# Output_v1_1.net
KiCad netlist of a schematic drawn in EAGLE
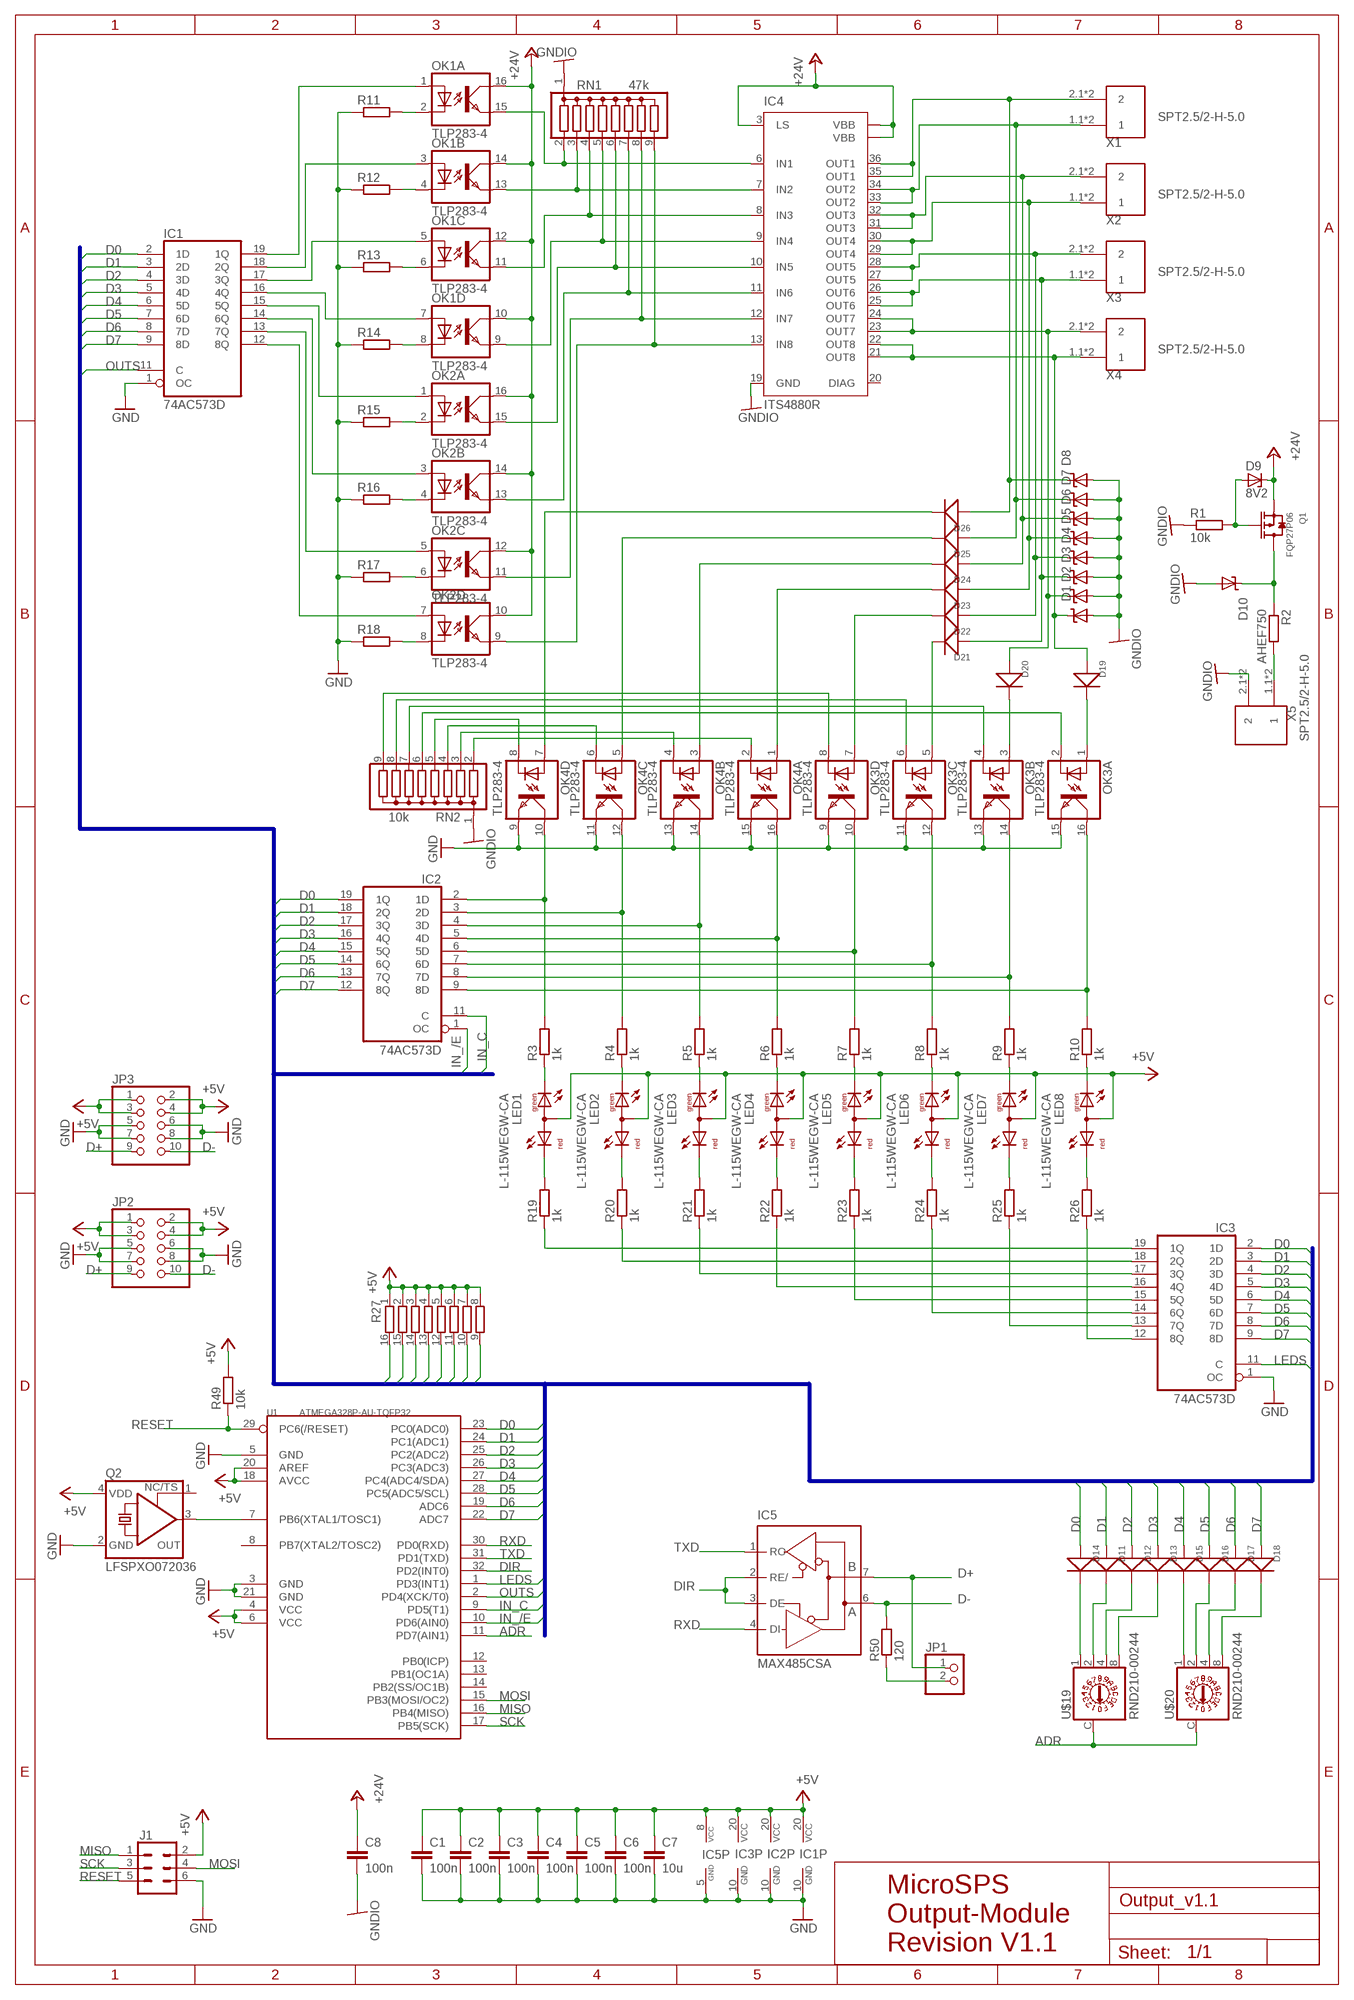
[diagram p0: schematic, sheet 1]

(export (version "E")
  (design (tool "Eeschema 10.0.6"))
  (components
    (comp (ref "C1")
      (value "100n")
      (footprint "eagle-import:C0805")
      (libsource (lib "eagle-import") (part "C-EUC0805"))
    )
    (comp (ref "C2")
      (value "100n")
      (footprint "eagle-import:C0805")
      (libsource (lib "eagle-import") (part "C-EUC0805"))
    )
    (comp (ref "C3")
      (value "100n")
      (footprint "eagle-import:C0805")
      (libsource (lib "eagle-import") (part "C-EUC0805"))
    )
    (comp (ref "C4")
      (value "100n")
      (footprint "eagle-import:C0805")
      (libsource (lib "eagle-import") (part "C-EUC0805"))
    )
    (comp (ref "C5")
      (value "100n")
      (footprint "eagle-import:C0805")
      (libsource (lib "eagle-import") (part "C-EUC0805"))
    )
    (comp (ref "C6")
      (value "100n")
      (footprint "eagle-import:C0805")
      (libsource (lib "eagle-import") (part "C-EUC0805"))
    )
    (comp (ref "C7")
      (value "10u")
      (footprint "eagle-import:C0805")
      (libsource (lib "eagle-import") (part "C-EUC0805"))
    )
    (comp (ref "C8")
      (value "100n")
      (footprint "eagle-import:C0805")
      (libsource (lib "eagle-import") (part "C-EUC0805"))
    )
    (comp (ref "D1")
      (value "SUPPRESSOR-SMBJ")
      (footprint "eagle-import:SMBJ")
      (libsource (lib "eagle-import") (part "SUPPRESSOR-SMBJ"))
    )
    (comp (ref "D2")
      (value "SUPPRESSOR-SMBJ")
      (footprint "eagle-import:SMBJ")
      (libsource (lib "eagle-import") (part "SUPPRESSOR-SMBJ"))
    )
    (comp (ref "D3")
      (value "SUPPRESSOR-SMBJ")
      (footprint "eagle-import:SMBJ")
      (libsource (lib "eagle-import") (part "SUPPRESSOR-SMBJ"))
    )
    (comp (ref "D4")
      (value "SUPPRESSOR-SMBJ")
      (footprint "eagle-import:SMBJ")
      (libsource (lib "eagle-import") (part "SUPPRESSOR-SMBJ"))
    )
    (comp (ref "D5")
      (value "SUPPRESSOR-SMBJ")
      (footprint "eagle-import:SMBJ")
      (libsource (lib "eagle-import") (part "SUPPRESSOR-SMBJ"))
    )
    (comp (ref "D6")
      (value "SUPPRESSOR-SMBJ")
      (footprint "eagle-import:SMBJ")
      (libsource (lib "eagle-import") (part "SUPPRESSOR-SMBJ"))
    )
    (comp (ref "D7")
      (value "SUPPRESSOR-SMBJ")
      (footprint "eagle-import:SMBJ")
      (libsource (lib "eagle-import") (part "SUPPRESSOR-SMBJ"))
    )
    (comp (ref "D8")
      (value "SUPPRESSOR-SMBJ")
      (footprint "eagle-import:SMBJ")
      (libsource (lib "eagle-import") (part "SUPPRESSOR-SMBJ"))
    )
    (comp (ref "D9")
      (value "8V2")
      (footprint "eagle-import:SOD80C")
      (libsource (lib "eagle-import") (part "ZENER-DIODESOD80C"))
    )
    (comp (ref "D10")
      (value "SUPPRESSOR-SMBJ")
      (footprint "eagle-import:SMBJ")
      (libsource (lib "eagle-import") (part "SUPPRESSOR-SMBJ"))
    )
    (comp (ref "D11")
      (value "DIODE'1N4148-SMD'")
      (footprint "eagle-import:LL-34")
      (libsource (lib "eagle-import") (part "DIODE'1N4148-SMD'"))
    )
    (comp (ref "D12")
      (value "DIODE'1N4148-SMD'")
      (footprint "eagle-import:LL-34")
      (libsource (lib "eagle-import") (part "DIODE'1N4148-SMD'"))
    )
    (comp (ref "D13")
      (value "DIODE'1N4148-SMD'")
      (footprint "eagle-import:LL-34")
      (libsource (lib "eagle-import") (part "DIODE'1N4148-SMD'"))
    )
    (comp (ref "D14")
      (value "DIODE'1N4148-SMD'")
      (footprint "eagle-import:LL-34")
      (libsource (lib "eagle-import") (part "DIODE'1N4148-SMD'"))
    )
    (comp (ref "D15")
      (value "DIODE'1N4148-SMD'")
      (footprint "eagle-import:LL-34")
      (libsource (lib "eagle-import") (part "DIODE'1N4148-SMD'"))
    )
    (comp (ref "D16")
      (value "DIODE'1N4148-SMD'")
      (footprint "eagle-import:LL-34")
      (libsource (lib "eagle-import") (part "DIODE'1N4148-SMD'"))
    )
    (comp (ref "D17")
      (value "DIODE'1N4148-SMD'")
      (footprint "eagle-import:LL-34")
      (libsource (lib "eagle-import") (part "DIODE'1N4148-SMD'"))
    )
    (comp (ref "D18")
      (value "DIODE'1N4148-SMD'")
      (footprint "eagle-import:LL-34")
      (libsource (lib "eagle-import") (part "DIODE'1N4148-SMD'"))
    )
    (comp (ref "D19")
      (value "DIODE'1N4148-SMD'")
      (footprint "eagle-import:LL-34")
      (libsource (lib "eagle-import") (part "DIODE'1N4148-SMD'"))
    )
    (comp (ref "D20")
      (value "DIODE'1N4148-SMD'")
      (footprint "eagle-import:LL-34")
      (libsource (lib "eagle-import") (part "DIODE'1N4148-SMD'"))
    )
    (comp (ref "D21")
      (value "DIODE'1N4148-SMD'")
      (footprint "eagle-import:LL-34")
      (libsource (lib "eagle-import") (part "DIODE'1N4148-SMD'"))
    )
    (comp (ref "D22")
      (value "DIODE'1N4148-SMD'")
      (footprint "eagle-import:LL-34")
      (libsource (lib "eagle-import") (part "DIODE'1N4148-SMD'"))
    )
    (comp (ref "D23")
      (value "DIODE'1N4148-SMD'")
      (footprint "eagle-import:LL-34")
      (libsource (lib "eagle-import") (part "DIODE'1N4148-SMD'"))
    )
    (comp (ref "D24")
      (value "DIODE'1N4148-SMD'")
      (footprint "eagle-import:LL-34")
      (libsource (lib "eagle-import") (part "DIODE'1N4148-SMD'"))
    )
    (comp (ref "D25")
      (value "DIODE'1N4148-SMD'")
      (footprint "eagle-import:LL-34")
      (libsource (lib "eagle-import") (part "DIODE'1N4148-SMD'"))
    )
    (comp (ref "D26")
      (value "DIODE'1N4148-SMD'")
      (footprint "eagle-import:LL-34")
      (libsource (lib "eagle-import") (part "DIODE'1N4148-SMD'"))
    )
    (comp (ref "IC1")
      (value "74AC573D")
      (footprint "eagle-import:SO20W")
      (libsource (lib "eagle-import") (part "74573DAC"))
    )
    (comp (ref "IC2")
      (value "74AC573D")
      (footprint "eagle-import:SO20W")
      (libsource (lib "eagle-import") (part "74573DAC"))
    )
    (comp (ref "IC3")
      (value "74AC573D")
      (footprint "eagle-import:SO20W")
      (libsource (lib "eagle-import") (part "74573DAC"))
    )
    (comp (ref "IC4")
      (value "ITS4880R")
      (footprint "eagle-import:PG-DSO-36")
      (libsource (lib "eagle-import") (part "ITS4880R"))
    )
    (comp (ref "IC5")
      (value "MAX485CSA")
      (footprint "eagle-import:SO08")
      (fields (field (name "MF") "MAXIM") (field (name "MPN") "MAX481CSA"))
      (libsource (lib "eagle-import") (part "MAX481CSA"))
    )
    (comp (ref "J1")
      (value "CONN_03X2FEMALE_SMD")
      (footprint "eagle-import:2X3_SMD")
      (libsource (lib "eagle-import") (part "CONN_03X2FEMALE_SMD"))
    )
    (comp (ref "JP1")
      (value "PINHD-1X2")
      (footprint "eagle-import:1X02")
      (libsource (lib "eagle-import") (part "PINHD-1X2"))
    )
    (comp (ref "JP2")
      (value "PINHD-2X5/90")
      (footprint "eagle-import:2X05_90")
      (libsource (lib "eagle-import") (part "PINHD-2X5/90"))
    )
    (comp (ref "JP3")
      (value "PINHD-2X5/90")
      (footprint "eagle-import:2X05_90")
      (libsource (lib "eagle-import") (part "PINHD-2X5/90"))
    )
    (comp (ref "LED1")
      (value "L-115WEGW-CA")
      (footprint "eagle-import:DUOLED-A-3MM")
      (libsource (lib "eagle-import") (part "L-115WEGW-CA"))
    )
    (comp (ref "LED2")
      (value "L-115WEGW-CA")
      (footprint "eagle-import:DUOLED-A-3MM")
      (libsource (lib "eagle-import") (part "L-115WEGW-CA"))
    )
    (comp (ref "LED3")
      (value "L-115WEGW-CA")
      (footprint "eagle-import:DUOLED-A-3MM")
      (libsource (lib "eagle-import") (part "L-115WEGW-CA"))
    )
    (comp (ref "LED4")
      (value "L-115WEGW-CA")
      (footprint "eagle-import:DUOLED-A-3MM")
      (libsource (lib "eagle-import") (part "L-115WEGW-CA"))
    )
    (comp (ref "LED5")
      (value "L-115WEGW-CA")
      (footprint "eagle-import:DUOLED-A-3MM")
      (libsource (lib "eagle-import") (part "L-115WEGW-CA"))
    )
    (comp (ref "LED6")
      (value "L-115WEGW-CA")
      (footprint "eagle-import:DUOLED-A-3MM")
      (libsource (lib "eagle-import") (part "L-115WEGW-CA"))
    )
    (comp (ref "LED7")
      (value "L-115WEGW-CA")
      (footprint "eagle-import:DUOLED-A-3MM")
      (libsource (lib "eagle-import") (part "L-115WEGW-CA"))
    )
    (comp (ref "LED8")
      (value "L-115WEGW-CA")
      (footprint "eagle-import:DUOLED-A-3MM")
      (libsource (lib "eagle-import") (part "L-115WEGW-CA"))
    )
    (comp (ref "OK1")
      (value "TLP283-4")
      (footprint "eagle-import:MINI-FLAT-16")
      (libsource (lib "eagle-import") (part "TLP283-4"))
    )
    (comp (ref "OK2")
      (value "TLP283-4")
      (footprint "eagle-import:MINI-FLAT-16")
      (libsource (lib "eagle-import") (part "TLP283-4"))
    )
    (comp (ref "OK3")
      (value "TLP283-4")
      (footprint "eagle-import:MINI-FLAT-16")
      (libsource (lib "eagle-import") (part "TLP283-4"))
    )
    (comp (ref "OK4")
      (value "TLP283-4")
      (footprint "eagle-import:MINI-FLAT-16")
      (libsource (lib "eagle-import") (part "TLP283-4"))
    )
    (comp (ref "Q1")
      (value "FQP27P06")
      (footprint "eagle-import:TO-220V")
      (libsource (lib "eagle-import") (part "DIP-MOSFET-P-CH-60V-27A-FQP27P06(TO-220)TO-220V"))
    )
    (comp (ref "Q2")
      (value "LFSPXO072036")
      (footprint "eagle-import:5.0X3.2_KXO-56")
      (libsource (lib "eagle-import") (part "KXO-PXO/XO-56-56"))
    )
    (comp (ref "R1")
      (value "10k")
      (footprint "eagle-import:R0805")
      (libsource (lib "eagle-import") (part "R-EU_R0805"))
    )
    (comp (ref "R2")
      (value "AHEF750")
      (footprint "eagle-import:0204_7")
      (libsource (lib "eagle-import") (part "resistor_R-EU_0204/7"))
    )
    (comp (ref "R3")
      (value "1k")
      (footprint "eagle-import:R0805")
      (libsource (lib "eagle-import") (part "R-EU_R0805"))
    )
    (comp (ref "R4")
      (value "1k")
      (footprint "eagle-import:R0805")
      (libsource (lib "eagle-import") (part "R-EU_R0805"))
    )
    (comp (ref "R5")
      (value "1k")
      (footprint "eagle-import:R0805")
      (libsource (lib "eagle-import") (part "R-EU_R0805"))
    )
    (comp (ref "R6")
      (value "1k")
      (footprint "eagle-import:R0805")
      (libsource (lib "eagle-import") (part "R-EU_R0805"))
    )
    (comp (ref "R7")
      (value "1k")
      (footprint "eagle-import:R0805")
      (libsource (lib "eagle-import") (part "R-EU_R0805"))
    )
    (comp (ref "R8")
      (value "1k")
      (footprint "eagle-import:R0805")
      (libsource (lib "eagle-import") (part "R-EU_R0805"))
    )
    (comp (ref "R9")
      (value "1k")
      (footprint "eagle-import:R0805")
      (libsource (lib "eagle-import") (part "R-EU_R0805"))
    )
    (comp (ref "R10")
      (value "1k")
      (footprint "eagle-import:R0805")
      (libsource (lib "eagle-import") (part "R-EU_R0805"))
    )
    (comp (ref "R11")
      (value "R-EU_R0805")
      (footprint "eagle-import:R0805")
      (libsource (lib "eagle-import") (part "R-EU_R0805"))
    )
    (comp (ref "R12")
      (value "R-EU_R0805")
      (footprint "eagle-import:R0805")
      (libsource (lib "eagle-import") (part "R-EU_R0805"))
    )
    (comp (ref "R13")
      (value "R-EU_R0805")
      (footprint "eagle-import:R0805")
      (libsource (lib "eagle-import") (part "R-EU_R0805"))
    )
    (comp (ref "R14")
      (value "R-EU_R0805")
      (footprint "eagle-import:R0805")
      (libsource (lib "eagle-import") (part "R-EU_R0805"))
    )
    (comp (ref "R15")
      (value "R-EU_R0805")
      (footprint "eagle-import:R0805")
      (libsource (lib "eagle-import") (part "R-EU_R0805"))
    )
    (comp (ref "R16")
      (value "R-EU_R0805")
      (footprint "eagle-import:R0805")
      (libsource (lib "eagle-import") (part "R-EU_R0805"))
    )
    (comp (ref "R17")
      (value "R-EU_R0805")
      (footprint "eagle-import:R0805")
      (libsource (lib "eagle-import") (part "R-EU_R0805"))
    )
    (comp (ref "R18")
      (value "R-EU_R0805")
      (footprint "eagle-import:R0805")
      (libsource (lib "eagle-import") (part "R-EU_R0805"))
    )
    (comp (ref "R19")
      (value "1k")
      (footprint "eagle-import:R0805")
      (libsource (lib "eagle-import") (part "R-EU_R0805"))
    )
    (comp (ref "R20")
      (value "1k")
      (footprint "eagle-import:R0805")
      (libsource (lib "eagle-import") (part "R-EU_R0805"))
    )
    (comp (ref "R21")
      (value "1k")
      (footprint "eagle-import:R0805")
      (libsource (lib "eagle-import") (part "R-EU_R0805"))
    )
    (comp (ref "R22")
      (value "1k")
      (footprint "eagle-import:R0805")
      (libsource (lib "eagle-import") (part "R-EU_R0805"))
    )
    (comp (ref "R23")
      (value "1k")
      (footprint "eagle-import:R0805")
      (libsource (lib "eagle-import") (part "R-EU_R0805"))
    )
    (comp (ref "R24")
      (value "1k")
      (footprint "eagle-import:R0805")
      (libsource (lib "eagle-import") (part "R-EU_R0805"))
    )
    (comp (ref "R25")
      (value "1k")
      (footprint "eagle-import:R0805")
      (libsource (lib "eagle-import") (part "R-EU_R0805"))
    )
    (comp (ref "R26")
      (value "1k")
      (footprint "eagle-import:R0805")
      (libsource (lib "eagle-import") (part "R-EU_R0805"))
    )
    (comp (ref "R27")
      (value "4816P-T01")
      (footprint "eagle-import:4816P")
      (fields (field (name "MF") "BOURNS, INC.") (field (name "MPN") "4816P-T01-684LF"))
      (libsource (lib "eagle-import") (part "4816P-T01"))
    )
    (comp (ref "R49")
      (value "10k")
      (footprint "eagle-import:R0805")
      (libsource (lib "eagle-import") (part "R-EU_R0805"))
    )
    (comp (ref "R50")
      (value "120")
      (footprint "eagle-import:R0805")
      (libsource (lib "eagle-import") (part "R-EU_R0805"))
    )
    (comp (ref "RN1")
      (value "47k")
      (footprint "eagle-import:SIL9")
      (libsource (lib "eagle-import") (part "G08R"))
    )
    (comp (ref "RN2")
      (value "10k")
      (footprint "eagle-import:SIL9")
      (libsource (lib "eagle-import") (part "G08R"))
    )
    (comp (ref "U$19")
      (value "RND210-00244")
      (footprint "eagle-import:RND210-00244")
      (libsource (lib "eagle-import") (part "RND210-00244"))
    )
    (comp (ref "U$20")
      (value "RND210-00244")
      (footprint "eagle-import:RND210-00244")
      (libsource (lib "eagle-import") (part "RND210-00244"))
    )
    (comp (ref "U1")
      (value "ATMEGA328P-AU-TQFP32")
      (footprint "eagle-import:TQFP32-0.8-7X7MM")
      (fields (field (name "MPN") "ATMEGA328P-AU"))
      (libsource (lib "eagle-import") (part "MCU-ATMEGA328P-AU(TQFP32)"))
    )
    (comp (ref "X1")
      (value "SPT2.5/2-H-5.0")
      (footprint "eagle-import:SPT2")
      (libsource (lib "eagle-import") (part "SPT2.5/2-H-5.0"))
    )
    (comp (ref "X2")
      (value "SPT2.5/2-H-5.0")
      (footprint "eagle-import:SPT2")
      (libsource (lib "eagle-import") (part "SPT2.5/2-H-5.0"))
    )
    (comp (ref "X3")
      (value "SPT2.5/2-H-5.0")
      (footprint "eagle-import:SPT2")
      (libsource (lib "eagle-import") (part "SPT2.5/2-H-5.0"))
    )
    (comp (ref "X4")
      (value "SPT2.5/2-H-5.0")
      (footprint "eagle-import:SPT2")
      (libsource (lib "eagle-import") (part "SPT2.5/2-H-5.0"))
    )
    (comp (ref "X5")
      (value "SPT2.5/2-H-5.0")
      (footprint "eagle-import:SPT2")
      (libsource (lib "eagle-import") (part "SPT2.5/2-H-5.0"))
    )
  )
  (nets
    (net (code "1") (name "+5V") (class "Default")
      (node (ref "C1") (pin "1") (pinfunction "1_1") (pintype "passive"))
      (node (ref "C2") (pin "1") (pinfunction "1_1") (pintype "passive"))
      (node (ref "C3") (pin "1") (pinfunction "1_1") (pintype "passive"))
      (node (ref "C4") (pin "1") (pinfunction "1_1") (pintype "passive"))
      (node (ref "C5") (pin "1") (pinfunction "1_1") (pintype "passive"))
      (node (ref "C6") (pin "1") (pinfunction "1_1") (pintype "passive"))
      (node (ref "C7") (pin "1") (pinfunction "1_1") (pintype "passive"))
      (node (ref "IC1") (pin "20") (pinfunction "VCC_20") (pintype "power_in"))
      (node (ref "IC2") (pin "20") (pinfunction "VCC_20") (pintype "power_in"))
      (node (ref "IC3") (pin "20") (pinfunction "VCC_20") (pintype "power_in"))
      (node (ref "IC5") (pin "8") (pinfunction "VCC_8") (pintype "power_in"))
      (node (ref "J1") (pin "2") (pinfunction "2_2") (pintype "bidirectional"))
      (node (ref "JP2") (pin "1") (pinfunction "1_1") (pintype "passive"))
      (node (ref "JP2") (pin "2") (pinfunction "2_2") (pintype "passive"))
      (node (ref "JP2") (pin "3") (pinfunction "3_3") (pintype "passive"))
      (node (ref "JP2") (pin "4") (pinfunction "4_4") (pintype "passive"))
      (node (ref "JP3") (pin "1") (pinfunction "1_1") (pintype "passive"))
      (node (ref "JP3") (pin "2") (pinfunction "2_2") (pintype "passive"))
      (node (ref "JP3") (pin "3") (pinfunction "3_3") (pintype "passive"))
      (node (ref "JP3") (pin "4") (pinfunction "4_4") (pintype "passive"))
      (node (ref "LED1") (pin "2") (pinfunction "A_2") (pintype "passive"))
      (node (ref "LED2") (pin "2") (pinfunction "A_2") (pintype "passive"))
      (node (ref "LED3") (pin "2") (pinfunction "A_2") (pintype "passive"))
      (node (ref "LED4") (pin "2") (pinfunction "A_2") (pintype "passive"))
      (node (ref "LED5") (pin "2") (pinfunction "A_2") (pintype "passive"))
      (node (ref "LED6") (pin "2") (pinfunction "A_2") (pintype "passive"))
      (node (ref "LED7") (pin "2") (pinfunction "A_2") (pintype "passive"))
      (node (ref "LED8") (pin "2") (pinfunction "A_2") (pintype "passive"))
      (node (ref "Q2") (pin "4") (pinfunction "VDD_4") (pintype "power_in"))
      (node (ref "R27") (pin "1") (pinfunction "1_1") (pintype "passive"))
      (node (ref "R27") (pin "2") (pinfunction "2_2") (pintype "passive"))
      (node (ref "R27") (pin "3") (pinfunction "3_3") (pintype "passive"))
      (node (ref "R27") (pin "4") (pinfunction "4_4") (pintype "passive"))
      (node (ref "R27") (pin "5") (pinfunction "5_5") (pintype "passive"))
      (node (ref "R27") (pin "6") (pinfunction "6_6") (pintype "passive"))
      (node (ref "R27") (pin "7") (pinfunction "7_7") (pintype "passive"))
      (node (ref "R27") (pin "8") (pinfunction "8_8") (pintype "passive"))
      (node (ref "R49") (pin "2") (pinfunction "2_2") (pintype "passive"))
      (node (ref "U1") (pin "18") (pinfunction "AVCC_18") (pintype "bidirectional"))
      (node (ref "U1") (pin "20") (pinfunction "AREF_20") (pintype "bidirectional"))
      (node (ref "U1") (pin "4") (pinfunction "VCC_4") (pintype "bidirectional"))
      (node (ref "U1") (pin "6") (pinfunction "VCC_6") (pintype "bidirectional"))
    )
    (net (code "2") (name "+24V") (class "Default")
      (node (ref "C8") (pin "1") (pinfunction "1_1") (pintype "passive"))
      (node (ref "D9") (pin "C") (pinfunction "C_C") (pintype "passive"))
      (node (ref "IC4") (pin "3") (pinfunction "LS_3") (pintype "input"))
      (node (ref "IC4") (pin "TH@1") (pinfunction "VBB_TH@1") (pintype "input"))
      (node (ref "IC4") (pin "TH@2") (pinfunction "VBB_TH@2") (pintype "input"))
      (node (ref "OK1") (pin "10") (pinfunction "COL_10") (pintype "passive"))
      (node (ref "OK1") (pin "12") (pinfunction "COL_12") (pintype "passive"))
      (node (ref "OK1") (pin "14") (pinfunction "COL_14") (pintype "passive"))
      (node (ref "OK1") (pin "16") (pinfunction "COL_16") (pintype "passive"))
      (node (ref "OK2") (pin "10") (pinfunction "COL_10") (pintype "passive"))
      (node (ref "OK2") (pin "12") (pinfunction "COL_12") (pintype "passive"))
      (node (ref "OK2") (pin "14") (pinfunction "COL_14") (pintype "passive"))
      (node (ref "OK2") (pin "16") (pinfunction "COL_16") (pintype "passive"))
      (node (ref "Q1") (pin "3") (pinfunction "S_3") (pintype "passive"))
    )
    (net (code "3") (name "/ADR") (class "Default")
      (node (ref "U$19") (pin "C") (pinfunction "C_C") (pintype "passive"))
      (node (ref "U$20") (pin "C") (pinfunction "C_C") (pintype "passive"))
      (node (ref "U1") (pin "11") (pinfunction "PD7(AIN1)_11") (pintype "bidirectional"))
    )
    (net (code "4") (name "/D+") (class "Default")
      (node (ref "IC5") (pin "7") (pinfunction "B_7") (pintype "passive"))
      (node (ref "JP1") (pin "1") (pinfunction "1_1") (pintype "passive"))
      (node (ref "JP2") (pin "9") (pinfunction "9_9") (pintype "passive"))
      (node (ref "JP3") (pin "9") (pinfunction "9_9") (pintype "passive"))
    )
    (net (code "5") (name "/D-") (class "Default")
      (node (ref "IC5") (pin "6") (pinfunction "A_6") (pintype "passive"))
      (node (ref "JP2") (pin "10") (pinfunction "10_10") (pintype "passive"))
      (node (ref "JP3") (pin "10") (pinfunction "10_10") (pintype "passive"))
      (node (ref "R50") (pin "2") (pinfunction "2_2") (pintype "passive"))
    )
    (net (code "6") (name "/D0") (class "Default")
      (node (ref "D14") (pin "A") (pinfunction "+_A") (pintype "passive"))
      (node (ref "IC1") (pin "2") (pinfunction "1D_2") (pintype "input"))
      (node (ref "IC2") (pin "19") (pinfunction "1Q_19") (pintype "tri_state"))
      (node (ref "IC3") (pin "2") (pinfunction "1D_2") (pintype "input"))
      (node (ref "R27") (pin "16") (pinfunction "16_16") (pintype "passive"))
      (node (ref "U1") (pin "23") (pinfunction "PC0(ADC0)_23") (pintype "bidirectional"))
    )
    (net (code "7") (name "/D1") (class "Default")
      (node (ref "D11") (pin "A") (pinfunction "+_A") (pintype "passive"))
      (node (ref "IC1") (pin "3") (pinfunction "2D_3") (pintype "input"))
      (node (ref "IC2") (pin "18") (pinfunction "2Q_18") (pintype "tri_state"))
      (node (ref "IC3") (pin "3") (pinfunction "2D_3") (pintype "input"))
      (node (ref "R27") (pin "15") (pinfunction "15_15") (pintype "passive"))
      (node (ref "U1") (pin "24") (pinfunction "PC1(ADC1)_24") (pintype "bidirectional"))
    )
    (net (code "8") (name "/D2") (class "Default")
      (node (ref "D12") (pin "A") (pinfunction "+_A") (pintype "passive"))
      (node (ref "IC1") (pin "4") (pinfunction "3D_4") (pintype "input"))
      (node (ref "IC2") (pin "17") (pinfunction "3Q_17") (pintype "tri_state"))
      (node (ref "IC3") (pin "4") (pinfunction "3D_4") (pintype "input"))
      (node (ref "R27") (pin "14") (pinfunction "14_14") (pintype "passive"))
      (node (ref "U1") (pin "25") (pinfunction "PC2(ADC2)_25") (pintype "bidirectional"))
    )
    (net (code "9") (name "/D3") (class "Default")
      (node (ref "D13") (pin "A") (pinfunction "+_A") (pintype "passive"))
      (node (ref "IC1") (pin "5") (pinfunction "4D_5") (pintype "input"))
      (node (ref "IC2") (pin "16") (pinfunction "4Q_16") (pintype "tri_state"))
      (node (ref "IC3") (pin "5") (pinfunction "4D_5") (pintype "input"))
      (node (ref "R27") (pin "13") (pinfunction "13_13") (pintype "passive"))
      (node (ref "U1") (pin "26") (pinfunction "PC3(ADC3)_26") (pintype "bidirectional"))
    )
    (net (code "10") (name "/D4") (class "Default")
      (node (ref "D15") (pin "A") (pinfunction "+_A") (pintype "passive"))
      (node (ref "IC1") (pin "6") (pinfunction "5D_6") (pintype "input"))
      (node (ref "IC2") (pin "15") (pinfunction "5Q_15") (pintype "tri_state"))
      (node (ref "IC3") (pin "6") (pinfunction "5D_6") (pintype "input"))
      (node (ref "R27") (pin "12") (pinfunction "12_12") (pintype "passive"))
      (node (ref "U1") (pin "27") (pinfunction "PC4(ADC4/SDA)_27") (pintype "bidirectional"))
    )
    (net (code "11") (name "/D5") (class "Default")
      (node (ref "D16") (pin "A") (pinfunction "+_A") (pintype "passive"))
      (node (ref "IC1") (pin "7") (pinfunction "6D_7") (pintype "input"))
      (node (ref "IC2") (pin "14") (pinfunction "6Q_14") (pintype "tri_state"))
      (node (ref "IC3") (pin "7") (pinfunction "6D_7") (pintype "input"))
      (node (ref "R27") (pin "11") (pinfunction "11_11") (pintype "passive"))
      (node (ref "U1") (pin "28") (pinfunction "PC5(ADC5/SCL)_28") (pintype "bidirectional"))
    )
    (net (code "12") (name "/D6") (class "Default")
      (node (ref "D17") (pin "A") (pinfunction "+_A") (pintype "passive"))
      (node (ref "IC1") (pin "8") (pinfunction "7D_8") (pintype "input"))
      (node (ref "IC2") (pin "13") (pinfunction "7Q_13") (pintype "tri_state"))
      (node (ref "IC3") (pin "8") (pinfunction "7D_8") (pintype "input"))
      (node (ref "R27") (pin "10") (pinfunction "10_10") (pintype "passive"))
      (node (ref "U1") (pin "19") (pinfunction "ADC6_19") (pintype "bidirectional"))
    )
    (net (code "13") (name "/D7") (class "Default")
      (node (ref "D18") (pin "A") (pinfunction "+_A") (pintype "passive"))
      (node (ref "IC1") (pin "9") (pinfunction "8D_9") (pintype "input"))
      (node (ref "IC2") (pin "12") (pinfunction "8Q_12") (pintype "tri_state"))
      (node (ref "IC3") (pin "9") (pinfunction "8D_9") (pintype "input"))
      (node (ref "R27") (pin "9") (pinfunction "9_9") (pintype "passive"))
      (node (ref "U1") (pin "22") (pinfunction "ADC7_22") (pintype "bidirectional"))
    )
    (net (code "14") (name "/DIR") (class "Default")
      (node (ref "IC5") (pin "2") (pinfunction "RE/_2") (pintype "input"))
      (node (ref "IC5") (pin "3") (pinfunction "DE_3") (pintype "input"))
      (node (ref "U1") (pin "32") (pinfunction "PD2(INT0)_32") (pintype "bidirectional"))
    )
    (net (code "15") (name "/IN_C") (class "Default")
      (node (ref "IC2") (pin "11") (pinfunction "C_11") (pintype "input"))
      (node (ref "U1") (pin "9") (pinfunction "PD5(T1)_9") (pintype "bidirectional"))
    )
    (net (code "16") (name "/IN_{slash}E") (class "Default")
      (node (ref "IC2") (pin "1") (pinfunction "OC_1") (pintype "input"))
      (node (ref "U1") (pin "10") (pinfunction "PD6(AIN0)_10") (pintype "bidirectional"))
    )
    (net (code "17") (name "/LEDS") (class "Default")
      (node (ref "IC3") (pin "11") (pinfunction "C_11") (pintype "input"))
      (node (ref "U1") (pin "1") (pinfunction "PD3(INT1)_1") (pintype "bidirectional"))
    )
    (net (code "18") (name "/MISO") (class "Default")
      (node (ref "J1") (pin "1") (pinfunction "1_1") (pintype "bidirectional"))
      (node (ref "U1") (pin "16") (pinfunction "PB4(MISO)_16") (pintype "bidirectional"))
    )
    (net (code "19") (name "/MOSI") (class "Default")
      (node (ref "J1") (pin "4") (pinfunction "4_4") (pintype "bidirectional"))
      (node (ref "U1") (pin "15") (pinfunction "PB3(MOSI/OC2)_15") (pintype "bidirectional"))
    )
    (net (code "20") (name "/OUTS") (class "Default")
      (node (ref "IC1") (pin "11") (pinfunction "C_11") (pintype "input"))
      (node (ref "U1") (pin "2") (pinfunction "PD4(XCK/T0)_2") (pintype "bidirectional"))
    )
    (net (code "21") (name "/RESET") (class "Default")
      (node (ref "J1") (pin "5") (pinfunction "5_5") (pintype "bidirectional"))
      (node (ref "R49") (pin "1") (pinfunction "1_1") (pintype "passive"))
      (node (ref "U1") (pin "29") (pinfunction "PC6(/RESET)_29") (pintype "bidirectional"))
    )
    (net (code "22") (name "/RXD") (class "Default")
      (node (ref "IC5") (pin "4") (pinfunction "DI_4") (pintype "input"))
      (node (ref "U1") (pin "30") (pinfunction "PD0(RXD)_30") (pintype "bidirectional"))
    )
    (net (code "23") (name "/SCK") (class "Default")
      (node (ref "J1") (pin "3") (pinfunction "3_3") (pintype "bidirectional"))
      (node (ref "U1") (pin "17") (pinfunction "PB5(SCK)_17") (pintype "bidirectional"))
    )
    (net (code "24") (name "/TXD") (class "Default")
      (node (ref "IC5") (pin "1") (pinfunction "RO_1") (pintype "output"))
      (node (ref "U1") (pin "31") (pinfunction "PD1(TXD)_31") (pintype "bidirectional"))
    )
    (net (code "25") (name "GND") (class "Default")
      (node (ref "C1") (pin "2") (pinfunction "2_2") (pintype "passive"))
      (node (ref "C2") (pin "2") (pinfunction "2_2") (pintype "passive"))
      (node (ref "C3") (pin "2") (pinfunction "2_2") (pintype "passive"))
      (node (ref "C4") (pin "2") (pinfunction "2_2") (pintype "passive"))
      (node (ref "C5") (pin "2") (pinfunction "2_2") (pintype "passive"))
      (node (ref "C6") (pin "2") (pinfunction "2_2") (pintype "passive"))
      (node (ref "C7") (pin "2") (pinfunction "2_2") (pintype "passive"))
      (node (ref "IC1") (pin "1") (pinfunction "OC_1") (pintype "input"))
      (node (ref "IC1") (pin "10") (pinfunction "GND_10") (pintype "power_in"))
      (node (ref "IC2") (pin "10") (pinfunction "GND_10") (pintype "power_in"))
      (node (ref "IC3") (pin "1") (pinfunction "OC_1") (pintype "input"))
      (node (ref "IC3") (pin "10") (pinfunction "GND_10") (pintype "power_in"))
      (node (ref "IC5") (pin "5") (pinfunction "GND_5") (pintype "power_in"))
      (node (ref "J1") (pin "6") (pinfunction "6_6") (pintype "bidirectional"))
      (node (ref "JP2") (pin "5") (pinfunction "5_5") (pintype "passive"))
      (node (ref "JP2") (pin "6") (pinfunction "6_6") (pintype "passive"))
      (node (ref "JP2") (pin "7") (pinfunction "7_7") (pintype "passive"))
      (node (ref "JP2") (pin "8") (pinfunction "8_8") (pintype "passive"))
      (node (ref "JP3") (pin "5") (pinfunction "5_5") (pintype "passive"))
      (node (ref "JP3") (pin "6") (pinfunction "6_6") (pintype "passive"))
      (node (ref "JP3") (pin "7") (pinfunction "7_7") (pintype "passive"))
      (node (ref "JP3") (pin "8") (pinfunction "8_8") (pintype "passive"))
      (node (ref "OK3") (pin "11") (pinfunction "EMIT_11") (pintype "passive"))
      (node (ref "OK3") (pin "13") (pinfunction "EMIT_13") (pintype "passive"))
      (node (ref "OK3") (pin "15") (pinfunction "EMIT_15") (pintype "passive"))
      (node (ref "OK3") (pin "9") (pinfunction "EMIT_9") (pintype "passive"))
      (node (ref "OK4") (pin "11") (pinfunction "EMIT_11") (pintype "passive"))
      (node (ref "OK4") (pin "13") (pinfunction "EMIT_13") (pintype "passive"))
      (node (ref "OK4") (pin "15") (pinfunction "EMIT_15") (pintype "passive"))
      (node (ref "OK4") (pin "9") (pinfunction "EMIT_9") (pintype "passive"))
      (node (ref "Q2") (pin "2") (pinfunction "GND_2") (pintype "power_in"))
      (node (ref "R11") (pin "1") (pinfunction "1_1") (pintype "passive"))
      (node (ref "R12") (pin "1") (pinfunction "1_1") (pintype "passive"))
      (node (ref "R13") (pin "1") (pinfunction "1_1") (pintype "passive"))
      (node (ref "R14") (pin "1") (pinfunction "1_1") (pintype "passive"))
      (node (ref "R15") (pin "1") (pinfunction "1_1") (pintype "passive"))
      (node (ref "R16") (pin "1") (pinfunction "1_1") (pintype "passive"))
      (node (ref "R17") (pin "1") (pinfunction "1_1") (pintype "passive"))
      (node (ref "R18") (pin "1") (pinfunction "1_1") (pintype "passive"))
      (node (ref "U1") (pin "21") (pinfunction "GND_21") (pintype "bidirectional"))
      (node (ref "U1") (pin "3") (pinfunction "GND_3") (pintype "bidirectional"))
      (node (ref "U1") (pin "5") (pinfunction "GND_5") (pintype "bidirectional"))
    )
    (net (code "26") (name "GNDIO") (class "Default")
      (node (ref "C8") (pin "2") (pinfunction "2_2") (pintype "passive"))
      (node (ref "D1") (pin "A") (pinfunction "A_A") (pintype "passive"))
      (node (ref "D10") (pin "A") (pinfunction "A_A") (pintype "passive"))
      (node (ref "D2") (pin "A") (pinfunction "A_A") (pintype "passive"))
      (node (ref "D3") (pin "A") (pinfunction "A_A") (pintype "passive"))
      (node (ref "D4") (pin "A") (pinfunction "A_A") (pintype "passive"))
      (node (ref "D5") (pin "A") (pinfunction "A_A") (pintype "passive"))
      (node (ref "D6") (pin "A") (pinfunction "A_A") (pintype "passive"))
      (node (ref "D7") (pin "A") (pinfunction "A_A") (pintype "passive"))
      (node (ref "D8") (pin "A") (pinfunction "A_A") (pintype "passive"))
      (node (ref "IC4") (pin "19") (pinfunction "GND_19") (pintype "power_in"))
      (node (ref "R1") (pin "1") (pinfunction "1_1") (pintype "passive"))
      (node (ref "RN1") (pin "1") (pinfunction "1_1") (pintype "passive"))
      (node (ref "RN2") (pin "1") (pinfunction "1_1") (pintype "passive"))
      (node (ref "X5") (pin "2.1") (pinfunction "2_2.1") (pintype "bidirectional"))
      (node (ref "X5") (pin "2.2") (pinfunction "2_2.2") (pintype "bidirectional"))
    )
    (net (code "27") (name "Net-(D11--)") (class "Default")
      (node (ref "D11") (pin "C") (pinfunction "-_C") (pintype "passive"))
      (node (ref "U$19") (pin "2") (pinfunction "2_2") (pintype "passive"))
    )
    (net (code "28") (name "Net-(D12--)") (class "Default")
      (node (ref "D12") (pin "C") (pinfunction "-_C") (pintype "passive"))
      (node (ref "U$19") (pin "4") (pinfunction "4_4") (pintype "passive"))
    )
    (net (code "29") (name "Net-(D13--)") (class "Default")
      (node (ref "D13") (pin "C") (pinfunction "-_C") (pintype "passive"))
      (node (ref "U$19") (pin "8") (pinfunction "8_8") (pintype "passive"))
    )
    (net (code "30") (name "Net-(D14--)") (class "Default")
      (node (ref "D14") (pin "C") (pinfunction "-_C") (pintype "passive"))
      (node (ref "U$19") (pin "1") (pinfunction "1_1") (pintype "passive"))
    )
    (net (code "31") (name "Net-(D15--)") (class "Default")
      (node (ref "D15") (pin "C") (pinfunction "-_C") (pintype "passive"))
      (node (ref "U$20") (pin "1") (pinfunction "1_1") (pintype "passive"))
    )
    (net (code "32") (name "Net-(D16--)") (class "Default")
      (node (ref "D16") (pin "C") (pinfunction "-_C") (pintype "passive"))
      (node (ref "U$20") (pin "2") (pinfunction "2_2") (pintype "passive"))
    )
    (net (code "33") (name "Net-(D17--)") (class "Default")
      (node (ref "D17") (pin "C") (pinfunction "-_C") (pintype "passive"))
      (node (ref "U$20") (pin "4") (pinfunction "4_4") (pintype "passive"))
    )
    (net (code "34") (name "Net-(D18--)") (class "Default")
      (node (ref "D18") (pin "C") (pinfunction "-_C") (pintype "passive"))
      (node (ref "U$20") (pin "8") (pinfunction "8_8") (pintype "passive"))
    )
    (net (code "35") (name "Net-(D19-+)") (class "Default")
      (node (ref "D1") (pin "C") (pinfunction "C_C") (pintype "passive"))
      (node (ref "D19") (pin "A") (pinfunction "+_A") (pintype "passive"))
      (node (ref "IC4") (pin "21") (pinfunction "OUT8_21") (pintype "output"))
      (node (ref "IC4") (pin "22") (pinfunction "OUT8_22") (pintype "output"))
      (node (ref "X4") (pin "1.1") (pinfunction "1_1.1") (pintype "bidirectional"))
      (node (ref "X4") (pin "1.2") (pinfunction "1_1.2") (pintype "bidirectional"))
    )
    (net (code "36") (name "Net-(D19--)") (class "Default")
      (node (ref "D19") (pin "C") (pinfunction "-_C") (pintype "passive"))
      (node (ref "OK3") (pin "1") (pinfunction "A_1") (pintype "passive"))
    )
    (net (code "37") (name "Net-(D20-+)") (class "Default")
      (node (ref "D2") (pin "C") (pinfunction "C_C") (pintype "passive"))
      (node (ref "D20") (pin "A") (pinfunction "+_A") (pintype "passive"))
      (node (ref "IC4") (pin "23") (pinfunction "OUT7_23") (pintype "output"))
      (node (ref "IC4") (pin "24") (pinfunction "OUT7_24") (pintype "output"))
      (node (ref "X4") (pin "2.1") (pinfunction "2_2.1") (pintype "bidirectional"))
      (node (ref "X4") (pin "2.2") (pinfunction "2_2.2") (pintype "bidirectional"))
    )
    (net (code "38") (name "Net-(D20--)") (class "Default")
      (node (ref "D20") (pin "C") (pinfunction "-_C") (pintype "passive"))
      (node (ref "OK3") (pin "3") (pinfunction "A_3") (pintype "passive"))
    )
    (net (code "39") (name "Net-(D21-+)") (class "Default")
      (node (ref "D21") (pin "A") (pinfunction "+_A") (pintype "passive"))
      (node (ref "D3") (pin "C") (pinfunction "C_C") (pintype "passive"))
      (node (ref "IC4") (pin "25") (pinfunction "OUT6_25") (pintype "output"))
      (node (ref "IC4") (pin "26") (pinfunction "OUT6_26") (pintype "output"))
      (node (ref "X3") (pin "1.1") (pinfunction "1_1.1") (pintype "bidirectional"))
      (node (ref "X3") (pin "1.2") (pinfunction "1_1.2") (pintype "bidirectional"))
    )
    (net (code "40") (name "Net-(D21--)") (class "Default")
      (node (ref "D21") (pin "C") (pinfunction "-_C") (pintype "passive"))
      (node (ref "OK3") (pin "5") (pinfunction "A_5") (pintype "passive"))
    )
    (net (code "41") (name "Net-(D22-+)") (class "Default")
      (node (ref "D22") (pin "A") (pinfunction "+_A") (pintype "passive"))
      (node (ref "D4") (pin "C") (pinfunction "C_C") (pintype "passive"))
      (node (ref "IC4") (pin "27") (pinfunction "OUT5_27") (pintype "output"))
      (node (ref "IC4") (pin "28") (pinfunction "OUT5_28") (pintype "output"))
      (node (ref "X3") (pin "2.1") (pinfunction "2_2.1") (pintype "bidirectional"))
      (node (ref "X3") (pin "2.2") (pinfunction "2_2.2") (pintype "bidirectional"))
    )
    (net (code "42") (name "Net-(D22--)") (class "Default")
      (node (ref "D22") (pin "C") (pinfunction "-_C") (pintype "passive"))
      (node (ref "OK3") (pin "7") (pinfunction "A_7") (pintype "passive"))
    )
    (net (code "43") (name "Net-(D23-+)") (class "Default")
      (node (ref "D23") (pin "A") (pinfunction "+_A") (pintype "passive"))
      (node (ref "D5") (pin "C") (pinfunction "C_C") (pintype "passive"))
      (node (ref "IC4") (pin "29") (pinfunction "OUT4_29") (pintype "output"))
      (node (ref "IC4") (pin "30") (pinfunction "OUT4_30") (pintype "output"))
      (node (ref "X2") (pin "1.1") (pinfunction "1_1.1") (pintype "bidirectional"))
      (node (ref "X2") (pin "1.2") (pinfunction "1_1.2") (pintype "bidirectional"))
    )
    (net (code "44") (name "Net-(D23--)") (class "Default")
      (node (ref "D23") (pin "C") (pinfunction "-_C") (pintype "passive"))
      (node (ref "OK4") (pin "1") (pinfunction "A_1") (pintype "passive"))
    )
    (net (code "45") (name "Net-(D24-+)") (class "Default")
      (node (ref "D24") (pin "A") (pinfunction "+_A") (pintype "passive"))
      (node (ref "D6") (pin "C") (pinfunction "C_C") (pintype "passive"))
      (node (ref "IC4") (pin "31") (pinfunction "OUT3_31") (pintype "output"))
      (node (ref "IC4") (pin "32") (pinfunction "OUT3_32") (pintype "output"))
      (node (ref "X2") (pin "2.1") (pinfunction "2_2.1") (pintype "bidirectional"))
      (node (ref "X2") (pin "2.2") (pinfunction "2_2.2") (pintype "bidirectional"))
    )
    (net (code "46") (name "Net-(D24--)") (class "Default")
      (node (ref "D24") (pin "C") (pinfunction "-_C") (pintype "passive"))
      (node (ref "OK4") (pin "3") (pinfunction "A_3") (pintype "passive"))
    )
    (net (code "47") (name "Net-(D25-+)") (class "Default")
      (node (ref "D25") (pin "A") (pinfunction "+_A") (pintype "passive"))
      (node (ref "D7") (pin "C") (pinfunction "C_C") (pintype "passive"))
      (node (ref "IC4") (pin "33") (pinfunction "OUT2_33") (pintype "output"))
      (node (ref "IC4") (pin "34") (pinfunction "OUT2_34") (pintype "output"))
      (node (ref "X1") (pin "1.1") (pinfunction "1_1.1") (pintype "bidirectional"))
      (node (ref "X1") (pin "1.2") (pinfunction "1_1.2") (pintype "bidirectional"))
    )
    (net (code "48") (name "Net-(D25--)") (class "Default")
      (node (ref "D25") (pin "C") (pinfunction "-_C") (pintype "passive"))
      (node (ref "OK4") (pin "5") (pinfunction "A_5") (pintype "passive"))
    )
    (net (code "49") (name "Net-(D26-+)") (class "Default")
      (node (ref "D26") (pin "A") (pinfunction "+_A") (pintype "passive"))
      (node (ref "D8") (pin "C") (pinfunction "C_C") (pintype "passive"))
      (node (ref "IC4") (pin "35") (pinfunction "OUT1_35") (pintype "output"))
      (node (ref "IC4") (pin "36") (pinfunction "OUT1_36") (pintype "output"))
      (node (ref "X1") (pin "2.1") (pinfunction "2_2.1") (pintype "bidirectional"))
      (node (ref "X1") (pin "2.2") (pinfunction "2_2.2") (pintype "bidirectional"))
    )
    (net (code "50") (name "Net-(D26--)") (class "Default")
      (node (ref "D26") (pin "C") (pinfunction "-_C") (pintype "passive"))
      (node (ref "OK4") (pin "7") (pinfunction "A_7") (pintype "passive"))
    )
    (net (code "51") (name "Net-(IC1A-1Q)") (class "Default")
      (node (ref "IC1") (pin "19") (pinfunction "1Q_19") (pintype "tri_state"))
      (node (ref "OK1") (pin "1") (pinfunction "A_1") (pintype "passive"))
    )
    (net (code "52") (name "Net-(IC1A-2Q)") (class "Default")
      (node (ref "IC1") (pin "18") (pinfunction "2Q_18") (pintype "tri_state"))
      (node (ref "OK1") (pin "3") (pinfunction "A_3") (pintype "passive"))
    )
    (net (code "53") (name "Net-(IC1A-3Q)") (class "Default")
      (node (ref "IC1") (pin "17") (pinfunction "3Q_17") (pintype "tri_state"))
      (node (ref "OK1") (pin "5") (pinfunction "A_5") (pintype "passive"))
    )
    (net (code "54") (name "Net-(IC1A-4Q)") (class "Default")
      (node (ref "IC1") (pin "16") (pinfunction "4Q_16") (pintype "tri_state"))
      (node (ref "OK1") (pin "7") (pinfunction "A_7") (pintype "passive"))
    )
    (net (code "55") (name "Net-(IC1A-5Q)") (class "Default")
      (node (ref "IC1") (pin "15") (pinfunction "5Q_15") (pintype "tri_state"))
      (node (ref "OK2") (pin "1") (pinfunction "A_1") (pintype "passive"))
    )
    (net (code "56") (name "Net-(IC1A-6Q)") (class "Default")
      (node (ref "IC1") (pin "14") (pinfunction "6Q_14") (pintype "tri_state"))
      (node (ref "OK2") (pin "3") (pinfunction "A_3") (pintype "passive"))
    )
    (net (code "57") (name "Net-(IC1A-7Q)") (class "Default")
      (node (ref "IC1") (pin "13") (pinfunction "7Q_13") (pintype "tri_state"))
      (node (ref "OK2") (pin "5") (pinfunction "A_5") (pintype "passive"))
    )
    (net (code "58") (name "Net-(IC1A-8Q)") (class "Default")
      (node (ref "IC1") (pin "12") (pinfunction "8Q_12") (pintype "tri_state"))
      (node (ref "OK2") (pin "7") (pinfunction "A_7") (pintype "passive"))
    )
    (net (code "59") (name "Net-(IC2A-1D)") (class "Default")
      (node (ref "IC2") (pin "2") (pinfunction "1D_2") (pintype "input"))
      (node (ref "OK4") (pin "10") (pinfunction "COL_10") (pintype "passive"))
      (node (ref "R3") (pin "2") (pinfunction "2_2") (pintype "passive"))
    )
    (net (code "60") (name "Net-(IC2A-2D)") (class "Default")
      (node (ref "IC2") (pin "3") (pinfunction "2D_3") (pintype "input"))
      (node (ref "OK4") (pin "12") (pinfunction "COL_12") (pintype "passive"))
      (node (ref "R4") (pin "2") (pinfunction "2_2") (pintype "passive"))
    )
    (net (code "61") (name "Net-(IC2A-3D)") (class "Default")
      (node (ref "IC2") (pin "4") (pinfunction "3D_4") (pintype "input"))
      (node (ref "OK4") (pin "14") (pinfunction "COL_14") (pintype "passive"))
      (node (ref "R5") (pin "2") (pinfunction "2_2") (pintype "passive"))
    )
    (net (code "62") (name "Net-(IC2A-4D)") (class "Default")
      (node (ref "IC2") (pin "5") (pinfunction "4D_5") (pintype "input"))
      (node (ref "OK4") (pin "16") (pinfunction "COL_16") (pintype "passive"))
      (node (ref "R6") (pin "2") (pinfunction "2_2") (pintype "passive"))
    )
    (net (code "63") (name "Net-(IC2A-5D)") (class "Default")
      (node (ref "IC2") (pin "6") (pinfunction "5D_6") (pintype "input"))
      (node (ref "OK3") (pin "10") (pinfunction "COL_10") (pintype "passive"))
      (node (ref "R7") (pin "2") (pinfunction "2_2") (pintype "passive"))
    )
    (net (code "64") (name "Net-(IC2A-6D)") (class "Default")
      (node (ref "IC2") (pin "7") (pinfunction "6D_7") (pintype "input"))
      (node (ref "OK3") (pin "12") (pinfunction "COL_12") (pintype "passive"))
      (node (ref "R8") (pin "2") (pinfunction "2_2") (pintype "passive"))
    )
    (net (code "65") (name "Net-(IC2A-7D)") (class "Default")
      (node (ref "IC2") (pin "8") (pinfunction "7D_8") (pintype "input"))
      (node (ref "OK3") (pin "14") (pinfunction "COL_14") (pintype "passive"))
      (node (ref "R9") (pin "2") (pinfunction "2_2") (pintype "passive"))
    )
    (net (code "66") (name "Net-(IC2A-8D)") (class "Default")
      (node (ref "IC2") (pin "9") (pinfunction "8D_9") (pintype "input"))
      (node (ref "OK3") (pin "16") (pinfunction "COL_16") (pintype "passive"))
      (node (ref "R10") (pin "2") (pinfunction "2_2") (pintype "passive"))
    )
    (net (code "67") (name "Net-(IC3A-1Q)") (class "Default")
      (node (ref "IC3") (pin "19") (pinfunction "1Q_19") (pintype "tri_state"))
      (node (ref "R19") (pin "1") (pinfunction "1_1") (pintype "passive"))
    )
    (net (code "68") (name "Net-(IC3A-2Q)") (class "Default")
      (node (ref "IC3") (pin "18") (pinfunction "2Q_18") (pintype "tri_state"))
      (node (ref "R20") (pin "1") (pinfunction "1_1") (pintype "passive"))
    )
    (net (code "69") (name "Net-(IC3A-3Q)") (class "Default")
      (node (ref "IC3") (pin "17") (pinfunction "3Q_17") (pintype "tri_state"))
      (node (ref "R21") (pin "1") (pinfunction "1_1") (pintype "passive"))
    )
    (net (code "70") (name "Net-(IC3A-4Q)") (class "Default")
      (node (ref "IC3") (pin "16") (pinfunction "4Q_16") (pintype "tri_state"))
      (node (ref "R22") (pin "1") (pinfunction "1_1") (pintype "passive"))
    )
    (net (code "71") (name "Net-(IC3A-5Q)") (class "Default")
      (node (ref "IC3") (pin "15") (pinfunction "5Q_15") (pintype "tri_state"))
      (node (ref "R23") (pin "1") (pinfunction "1_1") (pintype "passive"))
    )
    (net (code "72") (name "Net-(IC3A-6Q)") (class "Default")
      (node (ref "IC3") (pin "14") (pinfunction "6Q_14") (pintype "tri_state"))
      (node (ref "R24") (pin "1") (pinfunction "1_1") (pintype "passive"))
    )
    (net (code "73") (name "Net-(IC3A-7Q)") (class "Default")
      (node (ref "IC3") (pin "13") (pinfunction "7Q_13") (pintype "tri_state"))
      (node (ref "R25") (pin "1") (pinfunction "1_1") (pintype "passive"))
    )
    (net (code "74") (name "Net-(IC3A-8Q)") (class "Default")
      (node (ref "IC3") (pin "12") (pinfunction "8Q_12") (pintype "tri_state"))
      (node (ref "R26") (pin "1") (pinfunction "1_1") (pintype "passive"))
    )
    (net (code "75") (name "Net-(IC4-IN1)") (class "Default")
      (node (ref "IC4") (pin "6") (pinfunction "IN1_6") (pintype "input"))
      (node (ref "OK1") (pin "15") (pinfunction "EMIT_15") (pintype "passive"))
      (node (ref "RN1") (pin "2") (pinfunction "2_2") (pintype "passive"))
    )
    (net (code "76") (name "Net-(IC4-IN2)") (class "Default")
      (node (ref "IC4") (pin "7") (pinfunction "IN2_7") (pintype "input"))
      (node (ref "OK1") (pin "13") (pinfunction "EMIT_13") (pintype "passive"))
      (node (ref "RN1") (pin "3") (pinfunction "3_3") (pintype "passive"))
    )
    (net (code "77") (name "Net-(IC4-IN3)") (class "Default")
      (node (ref "IC4") (pin "8") (pinfunction "IN3_8") (pintype "input"))
      (node (ref "OK1") (pin "11") (pinfunction "EMIT_11") (pintype "passive"))
      (node (ref "RN1") (pin "4") (pinfunction "4_4") (pintype "passive"))
    )
    (net (code "78") (name "Net-(IC4-IN4)") (class "Default")
      (node (ref "IC4") (pin "9") (pinfunction "IN4_9") (pintype "input"))
      (node (ref "OK1") (pin "9") (pinfunction "EMIT_9") (pintype "passive"))
      (node (ref "RN1") (pin "5") (pinfunction "5_5") (pintype "passive"))
    )
    (net (code "79") (name "Net-(IC4-IN5)") (class "Default")
      (node (ref "IC4") (pin "10") (pinfunction "IN5_10") (pintype "input"))
      (node (ref "OK2") (pin "15") (pinfunction "EMIT_15") (pintype "passive"))
      (node (ref "RN1") (pin "6") (pinfunction "6_6") (pintype "passive"))
    )
    (net (code "80") (name "Net-(IC4-IN6)") (class "Default")
      (node (ref "IC4") (pin "11") (pinfunction "IN6_11") (pintype "input"))
      (node (ref "OK2") (pin "13") (pinfunction "EMIT_13") (pintype "passive"))
      (node (ref "RN1") (pin "7") (pinfunction "7_7") (pintype "passive"))
    )
    (net (code "81") (name "Net-(IC4-IN7)") (class "Default")
      (node (ref "IC4") (pin "12") (pinfunction "IN7_12") (pintype "input"))
      (node (ref "OK2") (pin "11") (pinfunction "EMIT_11") (pintype "passive"))
      (node (ref "RN1") (pin "8") (pinfunction "8_8") (pintype "passive"))
    )
    (net (code "82") (name "Net-(IC4-IN8)") (class "Default")
      (node (ref "IC4") (pin "13") (pinfunction "IN8_13") (pintype "input"))
      (node (ref "OK2") (pin "9") (pinfunction "EMIT_9") (pintype "passive"))
      (node (ref "RN1") (pin "9") (pinfunction "9_9") (pintype "passive"))
    )
    (net (code "83") (name "Net-(JP1-Pad2)") (class "Default")
      (node (ref "JP1") (pin "2") (pinfunction "2_2") (pintype "passive"))
      (node (ref "R50") (pin "1") (pinfunction "1_1") (pintype "passive"))
    )
    (net (code "84") (name "Net-(LED1-CG)") (class "Default")
      (node (ref "LED1") (pin "1") (pinfunction "CG_1") (pintype "passive"))
      (node (ref "R3") (pin "1") (pinfunction "1_1") (pintype "passive"))
    )
    (net (code "85") (name "Net-(LED1-CR)") (class "Default")
      (node (ref "LED1") (pin "3") (pinfunction "CR_3") (pintype "passive"))
      (node (ref "R19") (pin "2") (pinfunction "2_2") (pintype "passive"))
    )
    (net (code "86") (name "Net-(LED2-CG)") (class "Default")
      (node (ref "LED2") (pin "1") (pinfunction "CG_1") (pintype "passive"))
      (node (ref "R4") (pin "1") (pinfunction "1_1") (pintype "passive"))
    )
    (net (code "87") (name "Net-(LED2-CR)") (class "Default")
      (node (ref "LED2") (pin "3") (pinfunction "CR_3") (pintype "passive"))
      (node (ref "R20") (pin "2") (pinfunction "2_2") (pintype "passive"))
    )
    (net (code "88") (name "Net-(LED3-CG)") (class "Default")
      (node (ref "LED3") (pin "1") (pinfunction "CG_1") (pintype "passive"))
      (node (ref "R5") (pin "1") (pinfunction "1_1") (pintype "passive"))
    )
    (net (code "89") (name "Net-(LED3-CR)") (class "Default")
      (node (ref "LED3") (pin "3") (pinfunction "CR_3") (pintype "passive"))
      (node (ref "R21") (pin "2") (pinfunction "2_2") (pintype "passive"))
    )
    (net (code "90") (name "Net-(LED4-CG)") (class "Default")
      (node (ref "LED4") (pin "1") (pinfunction "CG_1") (pintype "passive"))
      (node (ref "R6") (pin "1") (pinfunction "1_1") (pintype "passive"))
    )
    (net (code "91") (name "Net-(LED4-CR)") (class "Default")
      (node (ref "LED4") (pin "3") (pinfunction "CR_3") (pintype "passive"))
      (node (ref "R22") (pin "2") (pinfunction "2_2") (pintype "passive"))
    )
    (net (code "92") (name "Net-(LED5-CG)") (class "Default")
      (node (ref "LED5") (pin "1") (pinfunction "CG_1") (pintype "passive"))
      (node (ref "R7") (pin "1") (pinfunction "1_1") (pintype "passive"))
    )
    (net (code "93") (name "Net-(LED5-CR)") (class "Default")
      (node (ref "LED5") (pin "3") (pinfunction "CR_3") (pintype "passive"))
      (node (ref "R23") (pin "2") (pinfunction "2_2") (pintype "passive"))
    )
    (net (code "94") (name "Net-(LED6-CG)") (class "Default")
      (node (ref "LED6") (pin "1") (pinfunction "CG_1") (pintype "passive"))
      (node (ref "R8") (pin "1") (pinfunction "1_1") (pintype "passive"))
    )
    (net (code "95") (name "Net-(LED6-CR)") (class "Default")
      (node (ref "LED6") (pin "3") (pinfunction "CR_3") (pintype "passive"))
      (node (ref "R24") (pin "2") (pinfunction "2_2") (pintype "passive"))
    )
    (net (code "96") (name "Net-(LED7-CG)") (class "Default")
      (node (ref "LED7") (pin "1") (pinfunction "CG_1") (pintype "passive"))
      (node (ref "R9") (pin "1") (pinfunction "1_1") (pintype "passive"))
    )
    (net (code "97") (name "Net-(LED7-CR)") (class "Default")
      (node (ref "LED7") (pin "3") (pinfunction "CR_3") (pintype "passive"))
      (node (ref "R25") (pin "2") (pinfunction "2_2") (pintype "passive"))
    )
    (net (code "98") (name "Net-(LED8-CG)") (class "Default")
      (node (ref "LED8") (pin "1") (pinfunction "CG_1") (pintype "passive"))
      (node (ref "R10") (pin "1") (pinfunction "1_1") (pintype "passive"))
    )
    (net (code "99") (name "Net-(LED8-CR)") (class "Default")
      (node (ref "LED8") (pin "3") (pinfunction "CR_3") (pintype "passive"))
      (node (ref "R26") (pin "2") (pinfunction "2_2") (pintype "passive"))
    )
    (net (code "100") (name "Net-(OK1A-C)") (class "Default")
      (node (ref "OK1") (pin "2") (pinfunction "C_2") (pintype "passive"))
      (node (ref "R11") (pin "2") (pinfunction "2_2") (pintype "passive"))
    )
    (net (code "101") (name "Net-(OK1B-C)") (class "Default")
      (node (ref "OK1") (pin "4") (pinfunction "C_4") (pintype "passive"))
      (node (ref "R12") (pin "2") (pinfunction "2_2") (pintype "passive"))
    )
    (net (code "102") (name "Net-(OK1C-C)") (class "Default")
      (node (ref "OK1") (pin "6") (pinfunction "C_6") (pintype "passive"))
      (node (ref "R13") (pin "2") (pinfunction "2_2") (pintype "passive"))
    )
    (net (code "103") (name "Net-(OK1D-C)") (class "Default")
      (node (ref "OK1") (pin "8") (pinfunction "C_8") (pintype "passive"))
      (node (ref "R14") (pin "2") (pinfunction "2_2") (pintype "passive"))
    )
    (net (code "104") (name "Net-(OK2A-C)") (class "Default")
      (node (ref "OK2") (pin "2") (pinfunction "C_2") (pintype "passive"))
      (node (ref "R15") (pin "2") (pinfunction "2_2") (pintype "passive"))
    )
    (net (code "105") (name "Net-(OK2B-C)") (class "Default")
      (node (ref "OK2") (pin "4") (pinfunction "C_4") (pintype "passive"))
      (node (ref "R16") (pin "2") (pinfunction "2_2") (pintype "passive"))
    )
    (net (code "106") (name "Net-(OK2C-C)") (class "Default")
      (node (ref "OK2") (pin "6") (pinfunction "C_6") (pintype "passive"))
      (node (ref "R17") (pin "2") (pinfunction "2_2") (pintype "passive"))
    )
    (net (code "107") (name "Net-(OK2D-C)") (class "Default")
      (node (ref "OK2") (pin "8") (pinfunction "C_8") (pintype "passive"))
      (node (ref "R18") (pin "2") (pinfunction "2_2") (pintype "passive"))
    )
    (net (code "108") (name "Net-(OK3A-C)") (class "Default")
      (node (ref "OK3") (pin "2") (pinfunction "C_2") (pintype "passive"))
      (node (ref "RN2") (pin "6") (pinfunction "6_6") (pintype "passive"))
    )
    (net (code "109") (name "Net-(OK3B-C)") (class "Default")
      (node (ref "OK3") (pin "4") (pinfunction "C_4") (pintype "passive"))
      (node (ref "RN2") (pin "7") (pinfunction "7_7") (pintype "passive"))
    )
    (net (code "110") (name "Net-(OK3C-C)") (class "Default")
      (node (ref "OK3") (pin "6") (pinfunction "C_6") (pintype "passive"))
      (node (ref "RN2") (pin "8") (pinfunction "8_8") (pintype "passive"))
    )
    (net (code "111") (name "Net-(OK3D-C)") (class "Default")
      (node (ref "OK3") (pin "8") (pinfunction "C_8") (pintype "passive"))
      (node (ref "RN2") (pin "9") (pinfunction "9_9") (pintype "passive"))
    )
    (net (code "112") (name "Net-(OK4A-C)") (class "Default")
      (node (ref "OK4") (pin "2") (pinfunction "C_2") (pintype "passive"))
      (node (ref "RN2") (pin "2") (pinfunction "2_2") (pintype "passive"))
    )
    (net (code "113") (name "Net-(OK4B-C)") (class "Default")
      (node (ref "OK4") (pin "4") (pinfunction "C_4") (pintype "passive"))
      (node (ref "RN2") (pin "3") (pinfunction "3_3") (pintype "passive"))
    )
    (net (code "114") (name "Net-(OK4C-C)") (class "Default")
      (node (ref "OK4") (pin "6") (pinfunction "C_6") (pintype "passive"))
      (node (ref "RN2") (pin "4") (pinfunction "4_4") (pintype "passive"))
    )
    (net (code "115") (name "Net-(OK4D-C)") (class "Default")
      (node (ref "OK4") (pin "8") (pinfunction "C_8") (pintype "passive"))
      (node (ref "RN2") (pin "5") (pinfunction "5_5") (pintype "passive"))
    )
    (net (code "116") (name "Net-(Q1-D)") (class "Default")
      (node (ref "D10") (pin "C") (pinfunction "C_C") (pintype "passive"))
      (node (ref "Q1") (pin "2") (pinfunction "D_2") (pintype "passive"))
      (node (ref "R2") (pin "1") (pinfunction "1_1") (pintype "passive"))
    )
    (net (code "117") (name "Net-(Q1-G)") (class "Default")
      (node (ref "D9") (pin "A") (pinfunction "A_A") (pintype "passive"))
      (node (ref "Q1") (pin "1") (pinfunction "G_1") (pintype "passive"))
      (node (ref "R1") (pin "2") (pinfunction "2_2") (pintype "passive"))
    )
    (net (code "118") (name "Net-(Q2-OUT)") (class "Default")
      (node (ref "Q2") (pin "3") (pinfunction "OUT_3") (pintype "output"))
      (node (ref "U1") (pin "7") (pinfunction "PB6(XTAL1/TOSC1)_7") (pintype "bidirectional"))
    )
    (net (code "119") (name "Net-(R2-Pad2)") (class "Default")
      (node (ref "R2") (pin "2") (pinfunction "2_2") (pintype "passive"))
      (node (ref "X5") (pin "1.1") (pinfunction "1_1.1") (pintype "bidirectional"))
      (node (ref "X5") (pin "1.2") (pinfunction "1_1.2") (pintype "bidirectional"))
    )
    (net (code "120") (name "unconnected-(IC4-DIAG-Pad20)") (class "Default")
      (node (ref "IC4") (pin "20") (pinfunction "DIAG_20") (pintype "output"))
    )
    (net (code "121") (name "unconnected-(Q2-TS-Pad1)") (class "Default")
      (node (ref "Q2") (pin "1") (pinfunction "TS_1") (pintype "passive"))
    )
    (net (code "122") (name "unconnected-(U1-PB0(ICP)-Pad12)") (class "Default")
      (node (ref "U1") (pin "12") (pinfunction "PB0(ICP)_12") (pintype "bidirectional"))
    )
    (net (code "123") (name "unconnected-(U1-PB1(OC1A)-Pad13)") (class "Default")
      (node (ref "U1") (pin "13") (pinfunction "PB1(OC1A)_13") (pintype "bidirectional"))
    )
    (net (code "124") (name "unconnected-(U1-PB2(SS{slash}OC1B)-Pad14)") (class "Default")
      (node (ref "U1") (pin "14") (pinfunction "PB2(SS/OC1B)_14") (pintype "bidirectional"))
    )
    (net (code "125") (name "unconnected-(U1-PB7(XTAL2{slash}TOSC2)-Pad8)") (class "Default")
      (node (ref "U1") (pin "8") (pinfunction "PB7(XTAL2/TOSC2)_8") (pintype "bidirectional"))
    )
  )
)
